# Zotino.net
KiCad netlist of a schematic drawn in Altium Designer
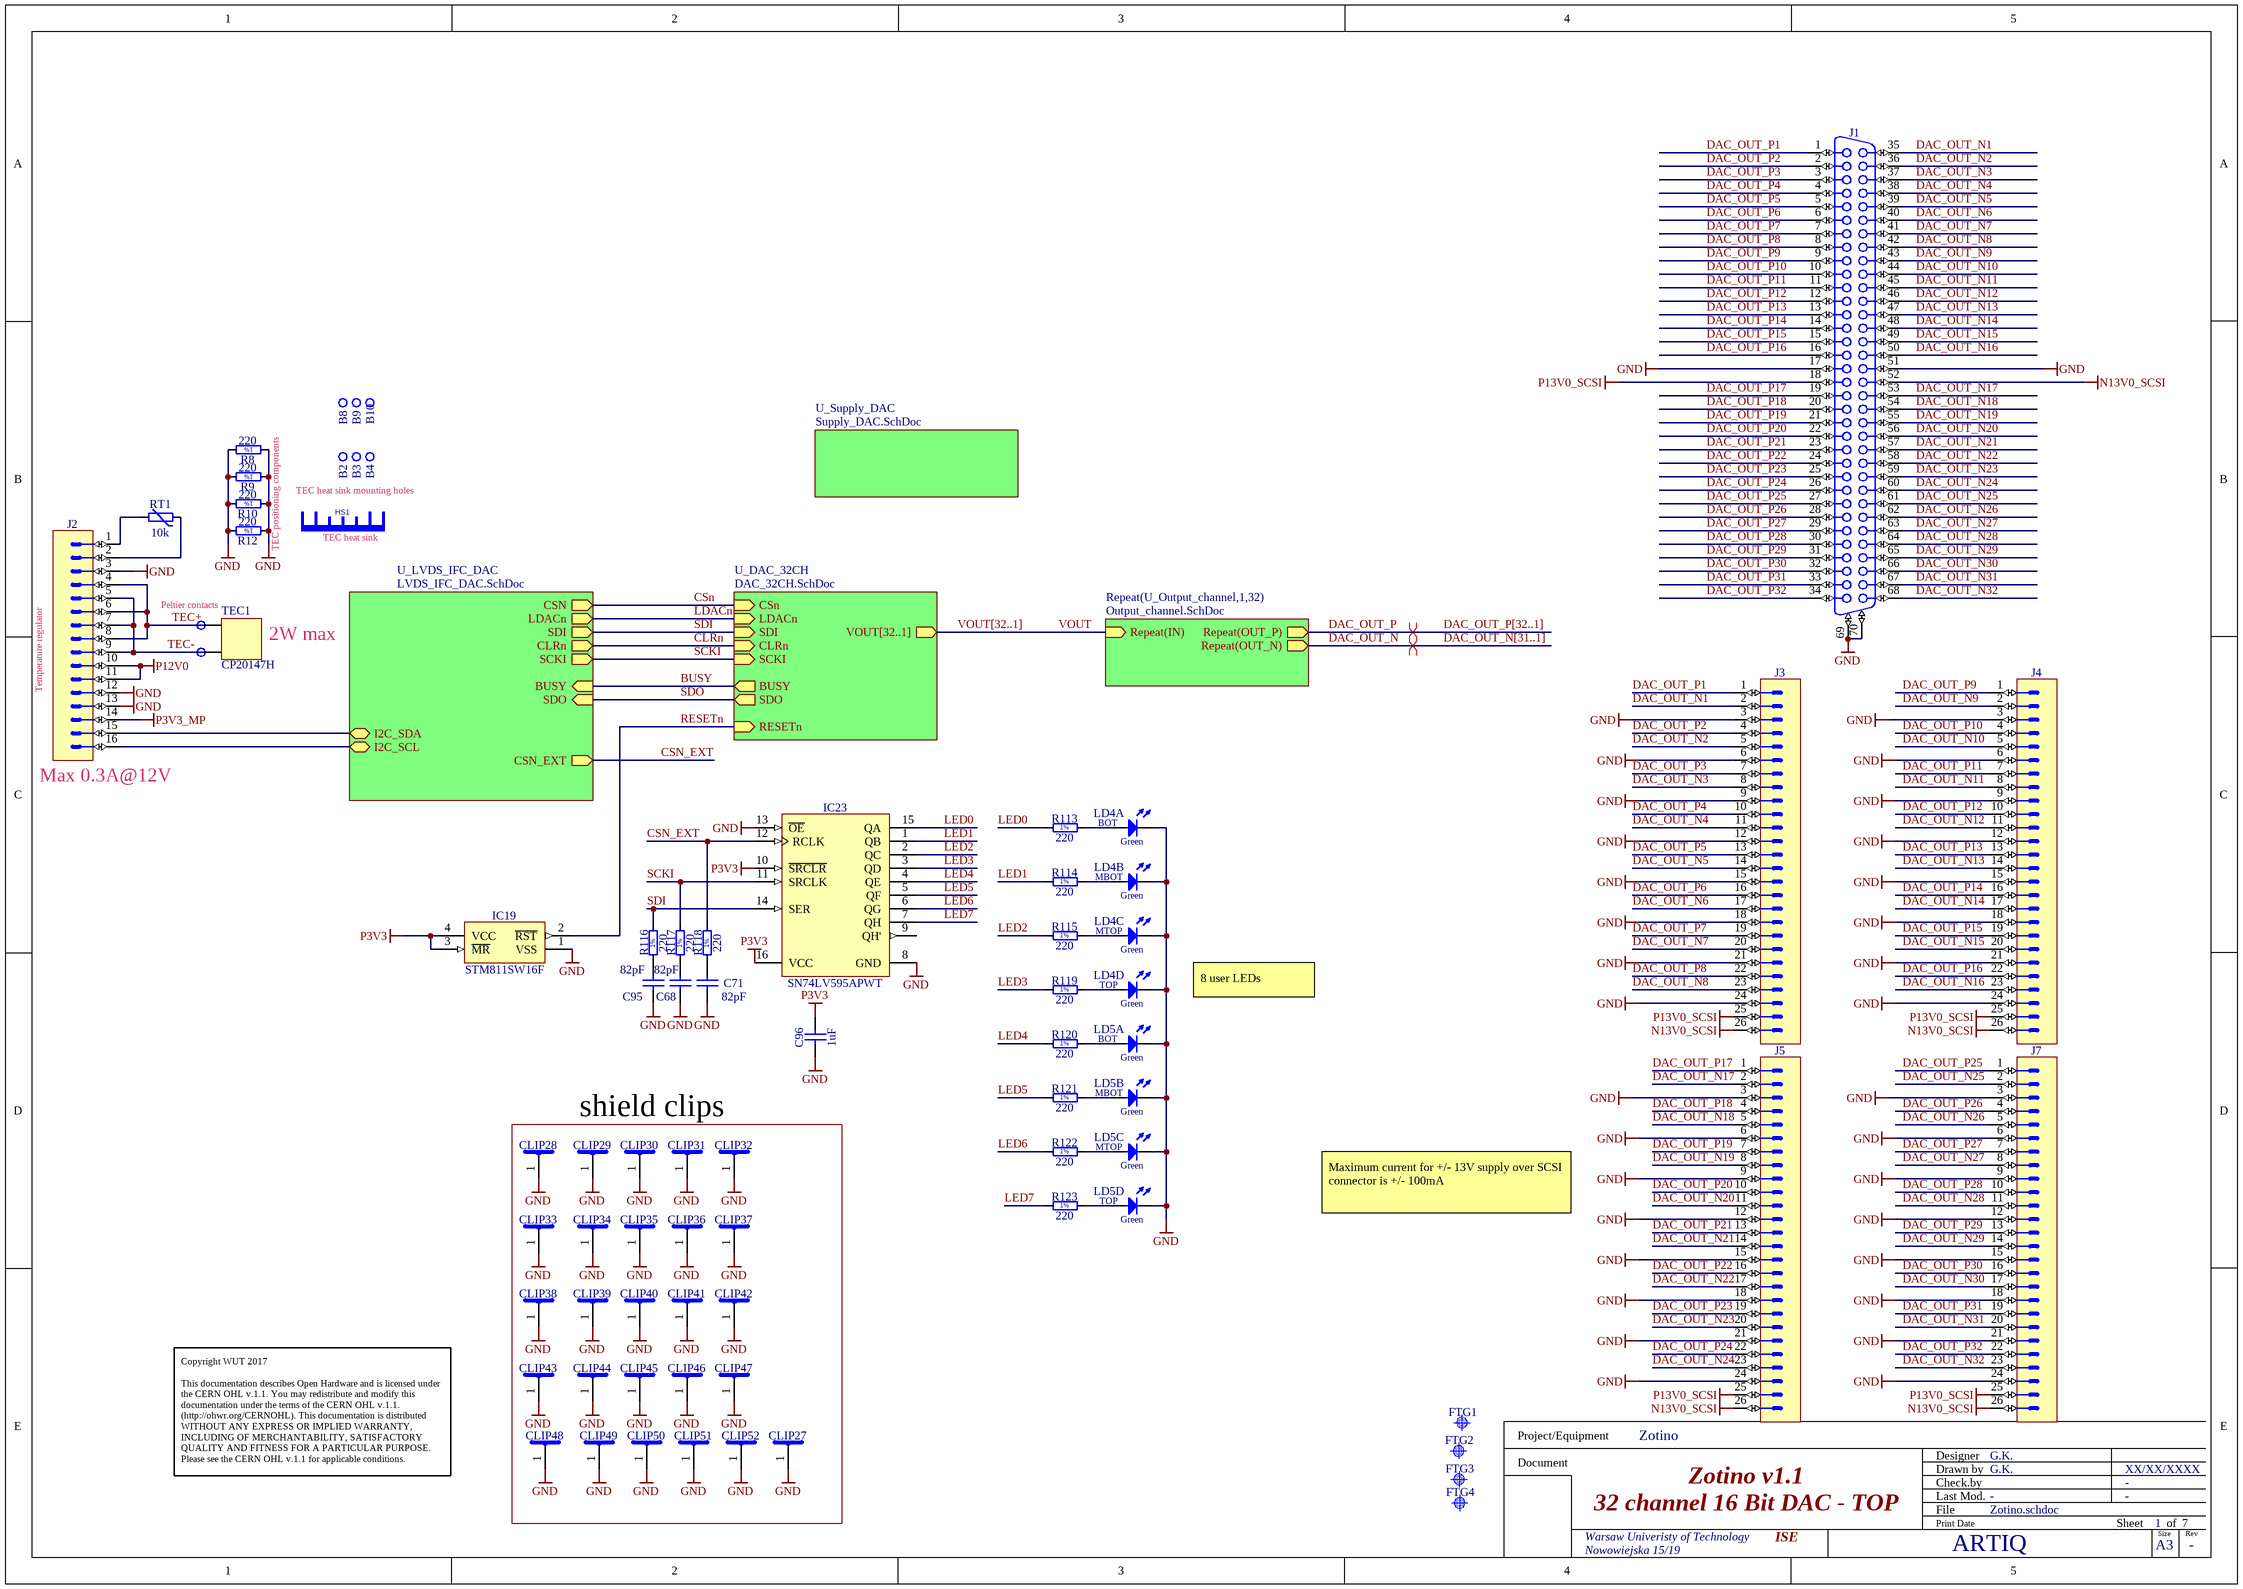
[diagram p0: Zotino.schdoc]

(export (version "E")
  (design (tool "Eeschema 10.0.6"))
  (components
    (comp (ref "B2")
      (value "Plated Hole")
      (footprint "c130h80")
      (description "Single Terminal Socket")
      (fields (field (name "PART NUMBER") "PLATED_HOLE0.8_PAD1.3") (field (name "AUTHOR") "CERN DEM JLC"))
      (libsource (lib "Eletro-mechanical") (part "Single Terminal Socket"))
    )
    (comp (ref "B3")
      (value "Plated Hole")
      (footprint "c130h80")
      (description "Single Terminal Socket")
      (fields (field (name "PART NUMBER") "PLATED_HOLE0.8_PAD1.3") (field (name "AUTHOR") "CERN DEM JLC"))
      (libsource (lib "Eletro-mechanical") (part "Single Terminal Socket"))
    )
    (comp (ref "B4")
      (value "Plated Hole")
      (footprint "c130h80")
      (description "Single Terminal Socket")
      (fields (field (name "PART NUMBER") "PLATED_HOLE0.8_PAD1.3") (field (name "AUTHOR") "CERN DEM JLC"))
      (libsource (lib "Eletro-mechanical") (part "Single Terminal Socket"))
    )
    (comp (ref "B5")
      (value "Plated Hole")
      (footprint "c160h110")
      (description "Single Terminal Socket")
      (fields (field (name "PART NUMBER") "PLATED_HOLE1.1_PAD1.6") (field (name "AUTHOR") "CERN DEM JLC"))
      (libsource (lib "Eletro-mechanical") (part "Single Terminal Socket"))
    )
    (comp (ref "B6")
      (value "Plated Hole")
      (footprint "c160h110")
      (description "Single Terminal Socket")
      (fields (field (name "PART NUMBER") "PLATED_HOLE1.1_PAD1.6") (field (name "AUTHOR") "CERN DEM JLC"))
      (libsource (lib "Eletro-mechanical") (part "Single Terminal Socket"))
    )
    (comp (ref "B8")
      (value "Plated Hole")
      (footprint "c130h80")
      (description "Single Terminal Socket")
      (fields (field (name "PART NUMBER") "PLATED_HOLE0.8_PAD1.3") (field (name "AUTHOR") "CERN DEM JLC"))
      (libsource (lib "Eletro-mechanical") (part "Single Terminal Socket"))
    )
    (comp (ref "B9")
      (value "Plated Hole")
      (footprint "c130h80")
      (description "Single Terminal Socket")
      (fields (field (name "PART NUMBER") "PLATED_HOLE0.8_PAD1.3") (field (name "AUTHOR") "CERN DEM JLC"))
      (libsource (lib "Eletro-mechanical") (part "Single Terminal Socket"))
    )
    (comp (ref "B10")
      (value "Plated Hole")
      (footprint "c130h80")
      (description "Single Terminal Socket")
      (fields (field (name "PART NUMBER") "PLATED_HOLE0.8_PAD1.3") (field (name "AUTHOR") "CERN DEM JLC"))
      (libsource (lib "Eletro-mechanical") (part "Single Terminal Socket"))
    )
    (comp (ref "C68")
      (value "82pF")
      (footprint "CAPC1608X87N")
      (description "Non-polarised capacitor")
      (fields
        (field (name "PART NUMBER") "CC0603_82PF_50V_5%_NP0")
        (field (name "VOLTAGE") "50V")
        (field (name "AUTHOR") "CERN DEM JLC")
      )
      (libsource (lib "Capacitors") (part "Capacitor - non polarized"))
    )
    (comp (ref "C71")
      (value "82pF")
      (footprint "CAPC1608X87N")
      (description "Non-polarised capacitor")
      (fields
        (field (name "PART NUMBER") "CC0603_82PF_50V_5%_NP0")
        (field (name "VOLTAGE") "50V")
        (field (name "AUTHOR") "CERN DEM JLC")
      )
      (libsource (lib "Capacitors") (part "Capacitor - non polarized"))
    )
    (comp (ref "C95")
      (value "82pF")
      (footprint "CAPC1608X87N")
      (description "Non-polarised capacitor")
      (fields
        (field (name "PART NUMBER") "CC0603_82PF_50V_5%_NP0")
        (field (name "VOLTAGE") "50V")
        (field (name "AUTHOR") "CERN DEM JLC")
      )
      (libsource (lib "Capacitors") (part "Capacitor - non polarized"))
    )
    (comp (ref "C96")
      (value "1uF")
      (footprint "CAPC1608X87N")
      (description "Non-polarised capacitor")
      (fields
        (field (name "PART NUMBER") "CC0603_1UF_25V_10%_X7R")
        (field (name "VOLTAGE") "25V")
        (field (name "AUTHOR") "CERN DEM JLC")
      )
      (libsource (lib "Capacitors") (part "Capacitor - non polarized"))
    )
    (comp (ref "CLIP27")
      (value "S1411-46R")
      (footprint "CLIP_HOLLAND-SHIELDING_LC")
      (description "Surface Mount Clip for PCB Screening Covers")
      (fields (field (name "MANUFACTURER") "HARWIN") (field (name "AUTHOR") "CERN DEM JLC"))
      (libsource (lib "LIBRARY_SCH") (part "SHIELD_CLIP"))
    )
    (comp (ref "CLIP28")
      (value "S1411-46R")
      (footprint "CLIP_HOLLAND-SHIELDING_LC")
      (description "Surface Mount Clip for PCB Screening Covers")
      (fields (field (name "MANUFACTURER") "HARWIN") (field (name "AUTHOR") "CERN DEM JLC"))
      (libsource (lib "LIBRARY_SCH") (part "SHIELD_CLIP"))
    )
    (comp (ref "CLIP29")
      (value "S1411-46R")
      (footprint "CLIP_HOLLAND-SHIELDING_LC")
      (description "Surface Mount Clip for PCB Screening Covers")
      (fields (field (name "MANUFACTURER") "HARWIN") (field (name "AUTHOR") "CERN DEM JLC"))
      (libsource (lib "LIBRARY_SCH") (part "SHIELD_CLIP"))
    )
    (comp (ref "CLIP30")
      (value "S1411-46R")
      (footprint "CLIP_HOLLAND-SHIELDING_LC")
      (description "Surface Mount Clip for PCB Screening Covers")
      (fields (field (name "MANUFACTURER") "HARWIN") (field (name "AUTHOR") "CERN DEM JLC"))
      (libsource (lib "LIBRARY_SCH") (part "SHIELD_CLIP"))
    )
    (comp (ref "CLIP31")
      (value "S1411-46R")
      (footprint "CLIP_HOLLAND-SHIELDING_LC")
      (description "Surface Mount Clip for PCB Screening Covers")
      (fields (field (name "MANUFACTURER") "HARWIN") (field (name "AUTHOR") "CERN DEM JLC"))
      (libsource (lib "LIBRARY_SCH") (part "SHIELD_CLIP"))
    )
    (comp (ref "CLIP32")
      (value "S1411-46R")
      (footprint "CLIP_HOLLAND-SHIELDING_LC")
      (description "Surface Mount Clip for PCB Screening Covers")
      (fields (field (name "MANUFACTURER") "HARWIN") (field (name "AUTHOR") "CERN DEM JLC"))
      (libsource (lib "LIBRARY_SCH") (part "SHIELD_CLIP"))
    )
    (comp (ref "CLIP33")
      (value "S1411-46R")
      (footprint "CLIP_HOLLAND-SHIELDING_LC")
      (description "Surface Mount Clip for PCB Screening Covers")
      (fields (field (name "MANUFACTURER") "HARWIN") (field (name "AUTHOR") "CERN DEM JLC"))
      (libsource (lib "LIBRARY_SCH") (part "SHIELD_CLIP"))
    )
    (comp (ref "CLIP34")
      (value "S1411-46R")
      (footprint "CLIP_HOLLAND-SHIELDING_LC")
      (description "Surface Mount Clip for PCB Screening Covers")
      (fields (field (name "MANUFACTURER") "HARWIN") (field (name "AUTHOR") "CERN DEM JLC"))
      (libsource (lib "LIBRARY_SCH") (part "SHIELD_CLIP"))
    )
    (comp (ref "CLIP35")
      (value "S1411-46R")
      (footprint "CLIP_HOLLAND-SHIELDING_LC")
      (description "Surface Mount Clip for PCB Screening Covers")
      (fields (field (name "MANUFACTURER") "HARWIN") (field (name "AUTHOR") "CERN DEM JLC"))
      (libsource (lib "LIBRARY_SCH") (part "SHIELD_CLIP"))
    )
    (comp (ref "CLIP36")
      (value "S1411-46R")
      (footprint "CLIP_HOLLAND-SHIELDING_LC")
      (description "Surface Mount Clip for PCB Screening Covers")
      (fields (field (name "MANUFACTURER") "HARWIN") (field (name "AUTHOR") "CERN DEM JLC"))
      (libsource (lib "LIBRARY_SCH") (part "SHIELD_CLIP"))
    )
    (comp (ref "CLIP37")
      (value "S1411-46R")
      (footprint "CLIP_HOLLAND-SHIELDING_LC")
      (description "Surface Mount Clip for PCB Screening Covers")
      (fields (field (name "MANUFACTURER") "HARWIN") (field (name "AUTHOR") "CERN DEM JLC"))
      (libsource (lib "LIBRARY_SCH") (part "SHIELD_CLIP"))
    )
    (comp (ref "CLIP38")
      (value "S1411-46R")
      (footprint "CLIP_HOLLAND-SHIELDING_LC")
      (description "Surface Mount Clip for PCB Screening Covers")
      (fields (field (name "MANUFACTURER") "HARWIN") (field (name "AUTHOR") "CERN DEM JLC"))
      (libsource (lib "LIBRARY_SCH") (part "SHIELD_CLIP"))
    )
    (comp (ref "CLIP39")
      (value "S1411-46R")
      (footprint "CLIP_HOLLAND-SHIELDING_LC")
      (description "Surface Mount Clip for PCB Screening Covers")
      (fields (field (name "MANUFACTURER") "HARWIN") (field (name "AUTHOR") "CERN DEM JLC"))
      (libsource (lib "LIBRARY_SCH") (part "SHIELD_CLIP"))
    )
    (comp (ref "CLIP40")
      (value "S1411-46R")
      (footprint "CLIP_HOLLAND-SHIELDING_LC")
      (description "Surface Mount Clip for PCB Screening Covers")
      (fields (field (name "MANUFACTURER") "HARWIN") (field (name "AUTHOR") "CERN DEM JLC"))
      (libsource (lib "LIBRARY_SCH") (part "SHIELD_CLIP"))
    )
    (comp (ref "CLIP41")
      (value "S1411-46R")
      (footprint "CLIP_HOLLAND-SHIELDING_LC")
      (description "Surface Mount Clip for PCB Screening Covers")
      (fields (field (name "MANUFACTURER") "HARWIN") (field (name "AUTHOR") "CERN DEM JLC"))
      (libsource (lib "LIBRARY_SCH") (part "SHIELD_CLIP"))
    )
    (comp (ref "CLIP42")
      (value "S1411-46R")
      (footprint "CLIP_HOLLAND-SHIELDING_LC")
      (description "Surface Mount Clip for PCB Screening Covers")
      (fields (field (name "MANUFACTURER") "HARWIN") (field (name "AUTHOR") "CERN DEM JLC"))
      (libsource (lib "LIBRARY_SCH") (part "SHIELD_CLIP"))
    )
    (comp (ref "CLIP43")
      (value "S1411-46R")
      (footprint "CLIP_HOLLAND-SHIELDING_LC")
      (description "Surface Mount Clip for PCB Screening Covers")
      (fields (field (name "MANUFACTURER") "HARWIN") (field (name "AUTHOR") "CERN DEM JLC"))
      (libsource (lib "LIBRARY_SCH") (part "SHIELD_CLIP"))
    )
    (comp (ref "CLIP44")
      (value "S1411-46R")
      (footprint "CLIP_HOLLAND-SHIELDING_LC")
      (description "Surface Mount Clip for PCB Screening Covers")
      (fields (field (name "MANUFACTURER") "HARWIN") (field (name "AUTHOR") "CERN DEM JLC"))
      (libsource (lib "LIBRARY_SCH") (part "SHIELD_CLIP"))
    )
    (comp (ref "CLIP45")
      (value "S1411-46R")
      (footprint "CLIP_HOLLAND-SHIELDING_LC")
      (description "Surface Mount Clip for PCB Screening Covers")
      (fields (field (name "MANUFACTURER") "HARWIN") (field (name "AUTHOR") "CERN DEM JLC"))
      (libsource (lib "LIBRARY_SCH") (part "SHIELD_CLIP"))
    )
    (comp (ref "CLIP46")
      (value "S1411-46R")
      (footprint "CLIP_HOLLAND-SHIELDING_LC")
      (description "Surface Mount Clip for PCB Screening Covers")
      (fields (field (name "MANUFACTURER") "HARWIN") (field (name "AUTHOR") "CERN DEM JLC"))
      (libsource (lib "LIBRARY_SCH") (part "SHIELD_CLIP"))
    )
    (comp (ref "CLIP47")
      (value "S1411-46R")
      (footprint "CLIP_HOLLAND-SHIELDING_LC")
      (description "Surface Mount Clip for PCB Screening Covers")
      (fields (field (name "MANUFACTURER") "HARWIN") (field (name "AUTHOR") "CERN DEM JLC"))
      (libsource (lib "LIBRARY_SCH") (part "SHIELD_CLIP"))
    )
    (comp (ref "CLIP48")
      (value "S1411-46R")
      (footprint "CLIP_HOLLAND-SHIELDING_LC")
      (description "Surface Mount Clip for PCB Screening Covers")
      (fields (field (name "MANUFACTURER") "HARWIN") (field (name "AUTHOR") "CERN DEM JLC"))
      (libsource (lib "LIBRARY_SCH") (part "SHIELD_CLIP"))
    )
    (comp (ref "CLIP49")
      (value "S1411-46R")
      (footprint "CLIP_HOLLAND-SHIELDING_LC")
      (description "Surface Mount Clip for PCB Screening Covers")
      (fields (field (name "MANUFACTURER") "HARWIN") (field (name "AUTHOR") "CERN DEM JLC"))
      (libsource (lib "LIBRARY_SCH") (part "SHIELD_CLIP"))
    )
    (comp (ref "CLIP50")
      (value "S1411-46R")
      (footprint "CLIP_HOLLAND-SHIELDING_LC")
      (description "Surface Mount Clip for PCB Screening Covers")
      (fields (field (name "MANUFACTURER") "HARWIN") (field (name "AUTHOR") "CERN DEM JLC"))
      (libsource (lib "LIBRARY_SCH") (part "SHIELD_CLIP"))
    )
    (comp (ref "CLIP51")
      (value "S1411-46R")
      (footprint "CLIP_HOLLAND-SHIELDING_LC")
      (description "Surface Mount Clip for PCB Screening Covers")
      (fields (field (name "MANUFACTURER") "HARWIN") (field (name "AUTHOR") "CERN DEM JLC"))
      (libsource (lib "LIBRARY_SCH") (part "SHIELD_CLIP"))
    )
    (comp (ref "CLIP52")
      (value "S1411-46R")
      (footprint "CLIP_HOLLAND-SHIELDING_LC")
      (description "Surface Mount Clip for PCB Screening Covers")
      (fields (field (name "MANUFACTURER") "HARWIN") (field (name "AUTHOR") "CERN DEM JLC"))
      (libsource (lib "LIBRARY_SCH") (part "SHIELD_CLIP"))
    )
    (comp (ref "FTG1")
      (value "Use only in PCB")
      (footprint "FIDUCIAL_TOP_C100-200")
      (description "Fiducial Target")
      (fields (field (name "PART NUMBER") "FIDUCIAL_TARGET_C100-200") (field (name "AUTHOR") "CERN DEM JLC"))
      (libsource (lib "Eletro-mechanical") (part "Fiducial Target"))
    )
    (comp (ref "FTG2")
      (value "Use only in PCB")
      (footprint "FIDUCIAL_TOP_S100-200")
      (description "Fiducial Target")
      (fields (field (name "PART NUMBER") "FIDUCIAL_TARGET_S100-200") (field (name "AUTHOR") "CERN DEM JLC"))
      (libsource (lib "Eletro-mechanical") (part "Fiducial Target"))
    )
    (comp (ref "FTG3")
      (value "Use only in PCB")
      (footprint "FIDUCIAL_TOP_S200-400")
      (description "Fiducial Target")
      (fields (field (name "PART NUMBER") "FIDUCIAL_TARGET_S200-400") (field (name "AUTHOR") "CERN DEM JLC"))
      (libsource (lib "Eletro-mechanical") (part "Fiducial Target"))
    )
    (comp (ref "FTG4")
      (value "Use only in PCB")
      (footprint "FIDUCIAL_TOP_S100-200")
      (description "Fiducial Target")
      (fields (field (name "PART NUMBER") "FIDUCIAL_TARGET_S100-200") (field (name "AUTHOR") "CERN DEM JLC"))
      (libsource (lib "Eletro-mechanical") (part "Fiducial Target"))
    )
    (comp (ref "HS1")
      (value "Heat Sink No Pad")
      (footprint "HSINK_ATS_ATS-X50190G-C1-R0")
      (description "Heat Sink Without Pad")
      (fields
        (field (name "PART NUMBER") "HSINK_ATS_ATS-X50190G-C1-R0")
        (field (name "MANUFACTURER") "ADVENCED THERMAL SOLUTION (ATS)")
        (field (name "AUTHOR") "GK")
      )
      (libsource (lib "LIBRARY_SCH") (part "HEAT_SINK_19x19"))
    )
    (comp (ref "IC19")
      (value "STM811SW16F")
      (footprint "SOT143N")
      (description "Microprocessor Reset Circuit")
      (fields (field (name "MANUFACTURER") "ST MICROELECTRONICS") (field (name "AUTHOR") "CERN DEM JLC"))
      (libsource (lib "ICs And Semiconductors") (part "STM811"))
    )
    (comp (ref "IC23")
      (value "SN74LV595APWT")
      (footprint "SOP65P640X120-16N")
      (description "8-Bit Shift Register With 3-State Output Register")
      (fields (field (name "MANUFACTURER") "TEXAS INSTRUMENTS") (field (name "AUTHOR") "CERN DEM JLC"))
      (libsource (lib "ICs And Semiconductors") (part "74595"))
    )
    (comp (ref "J1")
      (value "D-SUB")
      (footprint "TYCO_5787082-7")
      (description "68 contacts, AMPLIMITE .050\", Right Angled Receptacle Series III")
      (fields
        (field (name "PART NUMBER") "TYCO_5787082-7")
        (field (name "MANUFACTURER") "TYCO ELECTRONICS")
        (field (name "AUTHOR") "CERN DEM JLC")
      )
      (libsource (lib "Connectors") (part "TYCO_5787082-7"))
    )
    (comp (ref "J2")
      (value "Header 16")
      (footprint "3M_N2516-6002RB")
      (description "Connector 16 Male")
      (fields
        (field (name "PART NUMBER") "3M_N2516-6002RB")
        (field (name "MANUFACTURER") "3M")
        (field (name "AUTHOR") "CERN DEM JLC")
      )
      (libsource (lib "Connectors") (part "Connector 16 Male"))
    )
    (comp (ref "J3")
      (value "Header 26")
      (footprint "3M_N2526-6002RB")
      (description "Connector 26 Male")
      (fields
        (field (name "PART NUMBER") "3M_N2526-6002RB")
        (field (name "MANUFACTURER") "3M")
        (field (name "AUTHOR") "CERN DEM JLC")
      )
      (libsource (lib "Connectors") (part "Connector 26 Male"))
    )
    (comp (ref "J4")
      (value "Header 26")
      (footprint "3M_N2526-6002RB")
      (description "Connector 26 Male")
      (fields
        (field (name "PART NUMBER") "3M_N2526-6002RB")
        (field (name "MANUFACTURER") "3M")
        (field (name "AUTHOR") "CERN DEM JLC")
      )
      (libsource (lib "Connectors") (part "Connector 26 Male"))
    )
    (comp (ref "J5")
      (value "Header 26")
      (footprint "3M_N2526-6002RB")
      (description "Connector 26 Male")
      (fields
        (field (name "PART NUMBER") "3M_N2526-6002RB")
        (field (name "MANUFACTURER") "3M")
        (field (name "AUTHOR") "CERN DEM JLC")
      )
      (libsource (lib "Connectors") (part "Connector 26 Male"))
    )
    (comp (ref "J7")
      (value "Header 26")
      (footprint "3M_N2526-6002RB")
      (description "Connector 26 Male")
      (fields
        (field (name "PART NUMBER") "3M_N2526-6002RB")
        (field (name "MANUFACTURER") "3M")
        (field (name "AUTHOR") "CERN DEM JLC")
      )
      (libsource (lib "Connectors") (part "Connector 26 Male"))
    )
    (comp (ref "LD4")
      (value "Green")
      (footprint "LED_BIVAR_H485CGDL")
      (description "LED x4 Green 1C2A-BOT_3C4A_5C6A_7C8A-TOP")
      (fields
        (field (name "PART NUMBER") "LED_BIVAR_H485CGDL")
        (field (name "MANUFACTURER") "BIVAR")
        (field (name "AUTHOR") "CERN DEM JLC")
      )
      (libsource (lib "ICs And Semiconductors") (part "LED x4 Green 1C2A-BOT_3C4A_5C6A_7C8A-TOP"))
    )
    (comp (ref "LD5")
      (value "Green")
      (footprint "LED_BIVAR_H485CGDL")
      (description "LED x4 Green 1C2A-BOT_3C4A_5C6A_7C8A-TOP")
      (fields
        (field (name "PART NUMBER") "LED_BIVAR_H485CGDL")
        (field (name "MANUFACTURER") "BIVAR")
        (field (name "AUTHOR") "CERN DEM JLC")
      )
      (libsource (lib "ICs And Semiconductors") (part "LED x4 Green 1C2A-BOT_3C4A_5C6A_7C8A-TOP"))
    )
    (comp (ref "R8")
      (value "220")
      (footprint "RESC1608X55N")
      (description "Resistor - 1%")
      (fields
        (field (name "PART NUMBER") "R0603_220R_1%_0.1W_100PPM")
        (field (name "POWER") "0.1W")
        (field (name "AUTHOR") "CERN DEM JLC")
      )
      (libsource (lib "Resistors") (part "Resistor - 1%"))
    )
    (comp (ref "R9")
      (value "220")
      (footprint "RESC1608X55N")
      (description "Resistor - 1%")
      (fields
        (field (name "PART NUMBER") "R0603_220R_1%_0.1W_100PPM")
        (field (name "POWER") "0.1W")
        (field (name "AUTHOR") "CERN DEM JLC")
      )
      (libsource (lib "Resistors") (part "Resistor - 1%"))
    )
    (comp (ref "R10")
      (value "220")
      (footprint "RESC1608X55N")
      (description "Resistor - 1%")
      (fields
        (field (name "PART NUMBER") "R0603_220R_1%_0.1W_100PPM")
        (field (name "POWER") "0.1W")
        (field (name "AUTHOR") "CERN DEM JLC")
      )
      (libsource (lib "Resistors") (part "Resistor - 1%"))
    )
    (comp (ref "R12")
      (value "220")
      (footprint "RESC1608X55N")
      (description "Resistor - 1%")
      (fields
        (field (name "PART NUMBER") "R0603_220R_1%_0.1W_100PPM")
        (field (name "POWER") "0.1W")
        (field (name "AUTHOR") "CERN DEM JLC")
      )
      (libsource (lib "Resistors") (part "Resistor - 1%"))
    )
    (comp (ref "R113")
      (value "220")
      (footprint "RESC1608X55N")
      (description "Resistor - 1%")
      (fields
        (field (name "PART NUMBER") "R0603_220R_1%_0.1W_100PPM")
        (field (name "POWER") "0.1W")
        (field (name "AUTHOR") "CERN DEM JLC")
      )
      (libsource (lib "Resistors") (part "Resistor - 1%"))
    )
    (comp (ref "R114")
      (value "220")
      (footprint "RESC1608X55N")
      (description "Resistor - 1%")
      (fields
        (field (name "PART NUMBER") "R0603_220R_1%_0.1W_100PPM")
        (field (name "POWER") "0.1W")
        (field (name "AUTHOR") "CERN DEM JLC")
      )
      (libsource (lib "Resistors") (part "Resistor - 1%"))
    )
    (comp (ref "R115")
      (value "220")
      (footprint "RESC1608X55N")
      (description "Resistor - 1%")
      (fields
        (field (name "PART NUMBER") "R0603_220R_1%_0.1W_100PPM")
        (field (name "POWER") "0.1W")
        (field (name "AUTHOR") "CERN DEM JLC")
      )
      (libsource (lib "Resistors") (part "Resistor - 1%"))
    )
    (comp (ref "R116")
      (value "220")
      (footprint "RESC1608X55N")
      (description "Resistor - 1%")
      (fields
        (field (name "PART NUMBER") "R0603_220R_1%_0.1W_100PPM")
        (field (name "POWER") "0.1W")
        (field (name "AUTHOR") "CERN DEM JLC")
      )
      (libsource (lib "Resistors") (part "Resistor - 1%"))
    )
    (comp (ref "R117")
      (value "220")
      (footprint "RESC1608X55N")
      (description "Resistor - 1%")
      (fields
        (field (name "PART NUMBER") "R0603_220R_1%_0.1W_100PPM")
        (field (name "POWER") "0.1W")
        (field (name "AUTHOR") "CERN DEM JLC")
      )
      (libsource (lib "Resistors") (part "Resistor - 1%"))
    )
    (comp (ref "R118")
      (value "220")
      (footprint "RESC1608X55N")
      (description "Resistor - 1%")
      (fields
        (field (name "PART NUMBER") "R0603_220R_1%_0.1W_100PPM")
        (field (name "POWER") "0.1W")
        (field (name "AUTHOR") "CERN DEM JLC")
      )
      (libsource (lib "Resistors") (part "Resistor - 1%"))
    )
    (comp (ref "R119")
      (value "220")
      (footprint "RESC1608X55N")
      (description "Resistor - 1%")
      (fields
        (field (name "PART NUMBER") "R0603_220R_1%_0.1W_100PPM")
        (field (name "POWER") "0.1W")
        (field (name "AUTHOR") "CERN DEM JLC")
      )
      (libsource (lib "Resistors") (part "Resistor - 1%"))
    )
    (comp (ref "R120")
      (value "220")
      (footprint "RESC1608X55N")
      (description "Resistor - 1%")
      (fields
        (field (name "PART NUMBER") "R0603_220R_1%_0.1W_100PPM")
        (field (name "POWER") "0.1W")
        (field (name "AUTHOR") "CERN DEM JLC")
      )
      (libsource (lib "Resistors") (part "Resistor - 1%"))
    )
    (comp (ref "R121")
      (value "220")
      (footprint "RESC1608X55N")
      (description "Resistor - 1%")
      (fields
        (field (name "PART NUMBER") "R0603_220R_1%_0.1W_100PPM")
        (field (name "POWER") "0.1W")
        (field (name "AUTHOR") "CERN DEM JLC")
      )
      (libsource (lib "Resistors") (part "Resistor - 1%"))
    )
    (comp (ref "R122")
      (value "220")
      (footprint "RESC1608X55N")
      (description "Resistor - 1%")
      (fields
        (field (name "PART NUMBER") "R0603_220R_1%_0.1W_100PPM")
        (field (name "POWER") "0.1W")
        (field (name "AUTHOR") "CERN DEM JLC")
      )
      (libsource (lib "Resistors") (part "Resistor - 1%"))
    )
    (comp (ref "R123")
      (value "220")
      (footprint "RESC1608X55N")
      (description "Resistor - 1%")
      (fields
        (field (name "PART NUMBER") "R0603_220R_1%_0.1W_100PPM")
        (field (name "POWER") "0.1W")
        (field (name "AUTHOR") "CERN DEM JLC")
      )
      (libsource (lib "Resistors") (part "Resistor - 1%"))
    )
    (comp (ref "RT1")
      (value "10k")
      (footprint "THERMC1608X90N")
      (description "Thermistor NTC (Negative Temperature Coefficient)")
      (fields
        (field (name "PART NUMBER") "THERM_NTC_10K_EPCOS_B57330V2103J260")
        (field (name "POWER") "180mW")
        (field (name "AUTHOR") "CERN DEM BC")
      )
      (libsource (lib "Resistors") (part "Thermistor NTC"))
    )
    (comp (ref "TEC1")
      (value "CP20147H")
      (footprint "TEC_CP20147H")
      (description "Peltier Module 15x15 mm")
      (libsource (lib "LIBRARY_SCH") (part "TEC_CP20147H"))
    )
  )
  (nets
    (net (code "35") (name "/CSN_EXT") (class "Default")
      (node (ref "IC23") (pin "12") (pinfunction "RCLK_12") (pintype "input"))
      (node (ref "R118") (pin "2") (pinfunction "2_2") (pintype "passive"))
    )
    (net (code "38") (name "/DAC_OUT_N1") (class "Default")
      (node (ref "J1") (pin "35") (pinfunction "35_35") (pintype "bidirectional"))
      (node (ref "J3") (pin "2") (pinfunction "2_2") (pintype "bidirectional"))
    )
    (net (code "39") (name "/DAC_OUT_N2") (class "Default")
      (node (ref "J1") (pin "36") (pinfunction "36_36") (pintype "bidirectional"))
      (node (ref "J3") (pin "5") (pinfunction "5_5") (pintype "bidirectional"))
    )
    (net (code "40") (name "/DAC_OUT_N3") (class "Default")
      (node (ref "J1") (pin "37") (pinfunction "37_37") (pintype "bidirectional"))
      (node (ref "J3") (pin "8") (pinfunction "8_8") (pintype "bidirectional"))
    )
    (net (code "41") (name "/DAC_OUT_N4") (class "Default")
      (node (ref "J1") (pin "38") (pinfunction "38_38") (pintype "bidirectional"))
      (node (ref "J3") (pin "11") (pinfunction "11_11") (pintype "bidirectional"))
    )
    (net (code "42") (name "/DAC_OUT_N5") (class "Default")
      (node (ref "J1") (pin "39") (pinfunction "39_39") (pintype "bidirectional"))
      (node (ref "J3") (pin "14") (pinfunction "14_14") (pintype "bidirectional"))
    )
    (net (code "43") (name "/DAC_OUT_N6") (class "Default")
      (node (ref "J1") (pin "40") (pinfunction "40_40") (pintype "bidirectional"))
      (node (ref "J3") (pin "17") (pinfunction "17_17") (pintype "bidirectional"))
    )
    (net (code "44") (name "/DAC_OUT_N7") (class "Default")
      (node (ref "J1") (pin "41") (pinfunction "41_41") (pintype "bidirectional"))
      (node (ref "J3") (pin "20") (pinfunction "20_20") (pintype "bidirectional"))
    )
    (net (code "45") (name "/DAC_OUT_N8") (class "Default")
      (node (ref "J1") (pin "42") (pinfunction "42_42") (pintype "bidirectional"))
      (node (ref "J3") (pin "23") (pinfunction "23_23") (pintype "bidirectional"))
    )
    (net (code "46") (name "/DAC_OUT_N9") (class "Default")
      (node (ref "J1") (pin "43") (pinfunction "43_43") (pintype "bidirectional"))
      (node (ref "J4") (pin "2") (pinfunction "2_2") (pintype "bidirectional"))
    )
    (net (code "47") (name "/DAC_OUT_N10") (class "Default")
      (node (ref "J1") (pin "44") (pinfunction "44_44") (pintype "bidirectional"))
      (node (ref "J4") (pin "5") (pinfunction "5_5") (pintype "bidirectional"))
    )
    (net (code "48") (name "/DAC_OUT_N11") (class "Default")
      (node (ref "J1") (pin "45") (pinfunction "45_45") (pintype "bidirectional"))
      (node (ref "J4") (pin "8") (pinfunction "8_8") (pintype "bidirectional"))
    )
    (net (code "49") (name "/DAC_OUT_N12") (class "Default")
      (node (ref "J1") (pin "46") (pinfunction "46_46") (pintype "bidirectional"))
      (node (ref "J4") (pin "11") (pinfunction "11_11") (pintype "bidirectional"))
    )
    (net (code "50") (name "/DAC_OUT_N13") (class "Default")
      (node (ref "J1") (pin "47") (pinfunction "47_47") (pintype "bidirectional"))
      (node (ref "J4") (pin "14") (pinfunction "14_14") (pintype "bidirectional"))
    )
    (net (code "51") (name "/DAC_OUT_N14") (class "Default")
      (node (ref "J1") (pin "48") (pinfunction "48_48") (pintype "bidirectional"))
      (node (ref "J4") (pin "17") (pinfunction "17_17") (pintype "bidirectional"))
    )
    (net (code "52") (name "/DAC_OUT_N15") (class "Default")
      (node (ref "J1") (pin "49") (pinfunction "49_49") (pintype "bidirectional"))
      (node (ref "J4") (pin "20") (pinfunction "20_20") (pintype "bidirectional"))
    )
    (net (code "53") (name "/DAC_OUT_N16") (class "Default")
      (node (ref "J1") (pin "50") (pinfunction "50_50") (pintype "bidirectional"))
      (node (ref "J4") (pin "23") (pinfunction "23_23") (pintype "bidirectional"))
    )
    (net (code "54") (name "/DAC_OUT_N17") (class "Default")
      (node (ref "J1") (pin "53") (pinfunction "53_53") (pintype "bidirectional"))
      (node (ref "J5") (pin "2") (pinfunction "2_2") (pintype "bidirectional"))
    )
    (net (code "55") (name "/DAC_OUT_N18") (class "Default")
      (node (ref "J1") (pin "54") (pinfunction "54_54") (pintype "bidirectional"))
      (node (ref "J5") (pin "5") (pinfunction "5_5") (pintype "bidirectional"))
    )
    (net (code "56") (name "/DAC_OUT_N19") (class "Default")
      (node (ref "J1") (pin "55") (pinfunction "55_55") (pintype "bidirectional"))
      (node (ref "J5") (pin "8") (pinfunction "8_8") (pintype "bidirectional"))
    )
    (net (code "57") (name "/DAC_OUT_N20") (class "Default")
      (node (ref "J1") (pin "56") (pinfunction "56_56") (pintype "bidirectional"))
      (node (ref "J5") (pin "11") (pinfunction "11_11") (pintype "bidirectional"))
    )
    (net (code "58") (name "/DAC_OUT_N21") (class "Default")
      (node (ref "J1") (pin "57") (pinfunction "57_57") (pintype "bidirectional"))
      (node (ref "J5") (pin "14") (pinfunction "14_14") (pintype "bidirectional"))
    )
    (net (code "59") (name "/DAC_OUT_N22") (class "Default")
      (node (ref "J1") (pin "58") (pinfunction "58_58") (pintype "bidirectional"))
      (node (ref "J5") (pin "17") (pinfunction "17_17") (pintype "bidirectional"))
    )
    (net (code "60") (name "/DAC_OUT_N23") (class "Default")
      (node (ref "J1") (pin "59") (pinfunction "59_59") (pintype "bidirectional"))
      (node (ref "J5") (pin "20") (pinfunction "20_20") (pintype "bidirectional"))
    )
    (net (code "61") (name "/DAC_OUT_N24") (class "Default")
      (node (ref "J1") (pin "60") (pinfunction "60_60") (pintype "bidirectional"))
      (node (ref "J5") (pin "23") (pinfunction "23_23") (pintype "bidirectional"))
    )
    (net (code "62") (name "/DAC_OUT_N25") (class "Default")
      (node (ref "J1") (pin "61") (pinfunction "61_61") (pintype "bidirectional"))
      (node (ref "J7") (pin "2") (pinfunction "2_2") (pintype "bidirectional"))
    )
    (net (code "63") (name "/DAC_OUT_N26") (class "Default")
      (node (ref "J1") (pin "62") (pinfunction "62_62") (pintype "bidirectional"))
      (node (ref "J7") (pin "5") (pinfunction "5_5") (pintype "bidirectional"))
    )
    (net (code "64") (name "/DAC_OUT_N27") (class "Default")
      (node (ref "J1") (pin "63") (pinfunction "63_63") (pintype "bidirectional"))
      (node (ref "J7") (pin "8") (pinfunction "8_8") (pintype "bidirectional"))
    )
    (net (code "65") (name "/DAC_OUT_N28") (class "Default")
      (node (ref "J1") (pin "64") (pinfunction "64_64") (pintype "bidirectional"))
      (node (ref "J7") (pin "11") (pinfunction "11_11") (pintype "bidirectional"))
    )
    (net (code "66") (name "/DAC_OUT_N29") (class "Default")
      (node (ref "J1") (pin "65") (pinfunction "65_65") (pintype "bidirectional"))
      (node (ref "J7") (pin "14") (pinfunction "14_14") (pintype "bidirectional"))
    )
    (net (code "67") (name "/DAC_OUT_N30") (class "Default")
      (node (ref "J1") (pin "66") (pinfunction "66_66") (pintype "bidirectional"))
      (node (ref "J7") (pin "17") (pinfunction "17_17") (pintype "bidirectional"))
    )
    (net (code "68") (name "/DAC_OUT_N31") (class "Default")
      (node (ref "J1") (pin "67") (pinfunction "67_67") (pintype "bidirectional"))
      (node (ref "J7") (pin "20") (pinfunction "20_20") (pintype "bidirectional"))
    )
    (net (code "69") (name "/DAC_OUT_N32") (class "Default")
      (node (ref "J1") (pin "68") (pinfunction "68_68") (pintype "bidirectional"))
      (node (ref "J7") (pin "23") (pinfunction "23_23") (pintype "bidirectional"))
    )
    (net (code "72") (name "/DAC_OUT_P1") (class "Default")
      (node (ref "J1") (pin "1") (pinfunction "1_1") (pintype "bidirectional"))
      (node (ref "J3") (pin "1") (pinfunction "1_1") (pintype "bidirectional"))
    )
    (net (code "73") (name "/DAC_OUT_P2") (class "Default")
      (node (ref "J1") (pin "2") (pinfunction "2_2") (pintype "bidirectional"))
      (node (ref "J3") (pin "4") (pinfunction "4_4") (pintype "bidirectional"))
    )
    (net (code "74") (name "/DAC_OUT_P3") (class "Default")
      (node (ref "J1") (pin "3") (pinfunction "3_3") (pintype "bidirectional"))
      (node (ref "J3") (pin "7") (pinfunction "7_7") (pintype "bidirectional"))
    )
    (net (code "75") (name "/DAC_OUT_P4") (class "Default")
      (node (ref "J1") (pin "4") (pinfunction "4_4") (pintype "bidirectional"))
      (node (ref "J3") (pin "10") (pinfunction "10_10") (pintype "bidirectional"))
    )
    (net (code "76") (name "/DAC_OUT_P5") (class "Default")
      (node (ref "J1") (pin "5") (pinfunction "5_5") (pintype "bidirectional"))
      (node (ref "J3") (pin "13") (pinfunction "13_13") (pintype "bidirectional"))
    )
    (net (code "77") (name "/DAC_OUT_P6") (class "Default")
      (node (ref "J1") (pin "6") (pinfunction "6_6") (pintype "bidirectional"))
      (node (ref "J3") (pin "16") (pinfunction "16_16") (pintype "bidirectional"))
    )
    (net (code "78") (name "/DAC_OUT_P7") (class "Default")
      (node (ref "J1") (pin "7") (pinfunction "7_7") (pintype "bidirectional"))
      (node (ref "J3") (pin "19") (pinfunction "19_19") (pintype "bidirectional"))
    )
    (net (code "79") (name "/DAC_OUT_P8") (class "Default")
      (node (ref "J1") (pin "8") (pinfunction "8_8") (pintype "bidirectional"))
      (node (ref "J3") (pin "22") (pinfunction "22_22") (pintype "bidirectional"))
    )
    (net (code "80") (name "/DAC_OUT_P9") (class "Default")
      (node (ref "J1") (pin "9") (pinfunction "9_9") (pintype "bidirectional"))
      (node (ref "J4") (pin "1") (pinfunction "1_1") (pintype "bidirectional"))
    )
    (net (code "81") (name "/DAC_OUT_P10") (class "Default")
      (node (ref "J1") (pin "10") (pinfunction "10_10") (pintype "bidirectional"))
      (node (ref "J4") (pin "4") (pinfunction "4_4") (pintype "bidirectional"))
    )
    (net (code "82") (name "/DAC_OUT_P11") (class "Default")
      (node (ref "J1") (pin "11") (pinfunction "11_11") (pintype "bidirectional"))
      (node (ref "J4") (pin "7") (pinfunction "7_7") (pintype "bidirectional"))
    )
    (net (code "83") (name "/DAC_OUT_P12") (class "Default")
      (node (ref "J1") (pin "12") (pinfunction "12_12") (pintype "bidirectional"))
      (node (ref "J4") (pin "10") (pinfunction "10_10") (pintype "bidirectional"))
    )
    (net (code "84") (name "/DAC_OUT_P13") (class "Default")
      (node (ref "J1") (pin "13") (pinfunction "13_13") (pintype "bidirectional"))
      (node (ref "J4") (pin "13") (pinfunction "13_13") (pintype "bidirectional"))
    )
    (net (code "85") (name "/DAC_OUT_P14") (class "Default")
      (node (ref "J1") (pin "14") (pinfunction "14_14") (pintype "bidirectional"))
      (node (ref "J4") (pin "16") (pinfunction "16_16") (pintype "bidirectional"))
    )
    (net (code "86") (name "/DAC_OUT_P15") (class "Default")
      (node (ref "J1") (pin "15") (pinfunction "15_15") (pintype "bidirectional"))
      (node (ref "J4") (pin "19") (pinfunction "19_19") (pintype "bidirectional"))
    )
    (net (code "87") (name "/DAC_OUT_P16") (class "Default")
      (node (ref "J1") (pin "16") (pinfunction "16_16") (pintype "bidirectional"))
      (node (ref "J4") (pin "22") (pinfunction "22_22") (pintype "bidirectional"))
    )
    (net (code "88") (name "/DAC_OUT_P17") (class "Default")
      (node (ref "J1") (pin "19") (pinfunction "19_19") (pintype "bidirectional"))
      (node (ref "J5") (pin "1") (pinfunction "1_1") (pintype "bidirectional"))
    )
    (net (code "89") (name "/DAC_OUT_P18") (class "Default")
      (node (ref "J1") (pin "20") (pinfunction "20_20") (pintype "bidirectional"))
      (node (ref "J5") (pin "4") (pinfunction "4_4") (pintype "bidirectional"))
    )
    (net (code "90") (name "/DAC_OUT_P19") (class "Default")
      (node (ref "J1") (pin "21") (pinfunction "21_21") (pintype "bidirectional"))
      (node (ref "J5") (pin "7") (pinfunction "7_7") (pintype "bidirectional"))
    )
    (net (code "91") (name "/DAC_OUT_P20") (class "Default")
      (node (ref "J1") (pin "22") (pinfunction "22_22") (pintype "bidirectional"))
      (node (ref "J5") (pin "10") (pinfunction "10_10") (pintype "bidirectional"))
    )
    (net (code "92") (name "/DAC_OUT_P21") (class "Default")
      (node (ref "J1") (pin "23") (pinfunction "23_23") (pintype "bidirectional"))
      (node (ref "J5") (pin "13") (pinfunction "13_13") (pintype "bidirectional"))
    )
    (net (code "93") (name "/DAC_OUT_P22") (class "Default")
      (node (ref "J1") (pin "24") (pinfunction "24_24") (pintype "bidirectional"))
      (node (ref "J5") (pin "16") (pinfunction "16_16") (pintype "bidirectional"))
    )
    (net (code "94") (name "/DAC_OUT_P23") (class "Default")
      (node (ref "J1") (pin "25") (pinfunction "25_25") (pintype "bidirectional"))
      (node (ref "J5") (pin "19") (pinfunction "19_19") (pintype "bidirectional"))
    )
    (net (code "95") (name "/DAC_OUT_P24") (class "Default")
      (node (ref "J1") (pin "26") (pinfunction "26_26") (pintype "bidirectional"))
      (node (ref "J5") (pin "22") (pinfunction "22_22") (pintype "bidirectional"))
    )
    (net (code "96") (name "/DAC_OUT_P25") (class "Default")
      (node (ref "J1") (pin "27") (pinfunction "27_27") (pintype "bidirectional"))
      (node (ref "J7") (pin "1") (pinfunction "1_1") (pintype "bidirectional"))
    )
    (net (code "97") (name "/DAC_OUT_P26") (class "Default")
      (node (ref "J1") (pin "28") (pinfunction "28_28") (pintype "bidirectional"))
      (node (ref "J7") (pin "4") (pinfunction "4_4") (pintype "bidirectional"))
    )
    (net (code "98") (name "/DAC_OUT_P27") (class "Default")
      (node (ref "J1") (pin "29") (pinfunction "29_29") (pintype "bidirectional"))
      (node (ref "J7") (pin "7") (pinfunction "7_7") (pintype "bidirectional"))
    )
    (net (code "99") (name "/DAC_OUT_P28") (class "Default")
      (node (ref "J1") (pin "30") (pinfunction "30_30") (pintype "bidirectional"))
      (node (ref "J7") (pin "10") (pinfunction "10_10") (pintype "bidirectional"))
    )
    (net (code "100") (name "/DAC_OUT_P29") (class "Default")
      (node (ref "J1") (pin "31") (pinfunction "31_31") (pintype "bidirectional"))
      (node (ref "J7") (pin "13") (pinfunction "13_13") (pintype "bidirectional"))
    )
    (net (code "101") (name "/DAC_OUT_P30") (class "Default")
      (node (ref "J1") (pin "32") (pinfunction "32_32") (pintype "bidirectional"))
      (node (ref "J7") (pin "16") (pinfunction "16_16") (pintype "bidirectional"))
    )
    (net (code "102") (name "/DAC_OUT_P31") (class "Default")
      (node (ref "J1") (pin "33") (pinfunction "33_33") (pintype "bidirectional"))
      (node (ref "J7") (pin "19") (pinfunction "19_19") (pintype "bidirectional"))
    )
    (net (code "103") (name "/DAC_OUT_P32") (class "Default")
      (node (ref "J1") (pin "34") (pinfunction "34_34") (pintype "bidirectional"))
      (node (ref "J7") (pin "22") (pinfunction "22_22") (pintype "bidirectional"))
    )
    (net (code "105") (name "/I2C_SCL") (class "Default")
      (node (ref "J2") (pin "16") (pinfunction "16_16") (pintype "bidirectional"))
    )
    (net (code "106") (name "/I2C_SDA") (class "Default")
      (node (ref "J2") (pin "15") (pinfunction "15_15") (pintype "bidirectional"))
    )
    (net (code "108") (name "/LED0") (class "Default")
      (node (ref "IC23") (pin "15") (pinfunction "QA_15") (pintype "tri_state"))
      (node (ref "R113") (pin "1") (pinfunction "1_1") (pintype "passive"))
    )
    (net (code "109") (name "/LED1") (class "Default")
      (node (ref "IC23") (pin "1") (pinfunction "QB_1") (pintype "tri_state"))
      (node (ref "R114") (pin "1") (pinfunction "1_1") (pintype "passive"))
    )
    (net (code "110") (name "/LED2") (class "Default")
      (node (ref "IC23") (pin "2") (pinfunction "QC_2") (pintype "tri_state"))
      (node (ref "R115") (pin "1") (pinfunction "1_1") (pintype "passive"))
    )
    (net (code "111") (name "/LED3") (class "Default")
      (node (ref "IC23") (pin "3") (pinfunction "QD_3") (pintype "tri_state"))
      (node (ref "R119") (pin "1") (pinfunction "1_1") (pintype "passive"))
    )
    (net (code "112") (name "/LED4") (class "Default")
      (node (ref "IC23") (pin "4") (pinfunction "QE_4") (pintype "tri_state"))
      (node (ref "R120") (pin "1") (pinfunction "1_1") (pintype "passive"))
    )
    (net (code "113") (name "/LED5") (class "Default")
      (node (ref "IC23") (pin "5") (pinfunction "QF_5") (pintype "tri_state"))
      (node (ref "R121") (pin "1") (pinfunction "1_1") (pintype "passive"))
    )
    (net (code "114") (name "/LED6") (class "Default")
      (node (ref "IC23") (pin "6") (pinfunction "QG_6") (pintype "tri_state"))
      (node (ref "R122") (pin "1") (pinfunction "1_1") (pintype "passive"))
    )
    (net (code "115") (name "/LED7") (class "Default")
      (node (ref "IC23") (pin "7") (pinfunction "QH_7") (pintype "tri_state"))
      (node (ref "R123") (pin "1") (pinfunction "1_1") (pintype "passive"))
    )
    (net (code "116") (name "/RESETn") (class "Default")
      (node (ref "IC19") (pin "2") (pinfunction "~{RST}_2") (pintype "output"))
    )
    (net (code "117") (name "/SCKI") (class "Default")
      (node (ref "IC23") (pin "11") (pinfunction "SRCLK_11") (pintype "input"))
      (node (ref "R117") (pin "2") (pinfunction "2_2") (pintype "passive"))
    )
    (net (code "118") (name "/SDI") (class "Default")
      (node (ref "IC23") (pin "14") (pinfunction "SER_14") (pintype "input"))
      (node (ref "R116") (pin "2") (pinfunction "2_2") (pintype "passive"))
    )
    (net (code "120") (name "/TEC+") (class "Default")
      (node (ref "B5") (pin "1") (pinfunction "1_1") (pintype "bidirectional"))
      (node (ref "J2") (pin "4") (pinfunction "4_4") (pintype "bidirectional"))
      (node (ref "J2") (pin "6") (pinfunction "6_6") (pintype "bidirectional"))
      (node (ref "J2") (pin "8") (pinfunction "8_8") (pintype "bidirectional"))
    )
    (net (code "121") (name "/TEC-") (class "Default")
      (node (ref "B6") (pin "1") (pinfunction "1_1") (pintype "bidirectional"))
      (node (ref "J2") (pin "5") (pinfunction "5_5") (pintype "bidirectional"))
      (node (ref "J2") (pin "7") (pinfunction "7_7") (pintype "bidirectional"))
      (node (ref "J2") (pin "9") (pinfunction "9_9") (pintype "bidirectional"))
    )
    (net (code "124") (name "GND") (class "Default")
      (node (ref "C68") (pin "1") (pinfunction "1_1") (pintype "passive"))
      (node (ref "C71") (pin "1") (pinfunction "1_1") (pintype "passive"))
      (node (ref "C95") (pin "1") (pinfunction "1_1") (pintype "passive"))
      (node (ref "C96") (pin "1") (pinfunction "1_1") (pintype "passive"))
      (node (ref "CLIP27") (pin "1") (pinfunction "1_1") (pintype "passive"))
      (node (ref "CLIP28") (pin "1") (pinfunction "1_1") (pintype "passive"))
      (node (ref "CLIP29") (pin "1") (pinfunction "1_1") (pintype "passive"))
      (node (ref "CLIP30") (pin "1") (pinfunction "1_1") (pintype "passive"))
      (node (ref "CLIP31") (pin "1") (pinfunction "1_1") (pintype "passive"))
      (node (ref "CLIP32") (pin "1") (pinfunction "1_1") (pintype "passive"))
      (node (ref "CLIP33") (pin "1") (pinfunction "1_1") (pintype "passive"))
      (node (ref "CLIP34") (pin "1") (pinfunction "1_1") (pintype "passive"))
      (node (ref "CLIP35") (pin "1") (pinfunction "1_1") (pintype "passive"))
      (node (ref "CLIP36") (pin "1") (pinfunction "1_1") (pintype "passive"))
      (node (ref "CLIP37") (pin "1") (pinfunction "1_1") (pintype "passive"))
      (node (ref "CLIP38") (pin "1") (pinfunction "1_1") (pintype "passive"))
      (node (ref "CLIP39") (pin "1") (pinfunction "1_1") (pintype "passive"))
      (node (ref "CLIP40") (pin "1") (pinfunction "1_1") (pintype "passive"))
      (node (ref "CLIP41") (pin "1") (pinfunction "1_1") (pintype "passive"))
      (node (ref "CLIP42") (pin "1") (pinfunction "1_1") (pintype "passive"))
      (node (ref "CLIP43") (pin "1") (pinfunction "1_1") (pintype "passive"))
      (node (ref "CLIP44") (pin "1") (pinfunction "1_1") (pintype "passive"))
      (node (ref "CLIP45") (pin "1") (pinfunction "1_1") (pintype "passive"))
      (node (ref "CLIP46") (pin "1") (pinfunction "1_1") (pintype "passive"))
      (node (ref "CLIP47") (pin "1") (pinfunction "1_1") (pintype "passive"))
      (node (ref "CLIP48") (pin "1") (pinfunction "1_1") (pintype "passive"))
      (node (ref "CLIP49") (pin "1") (pinfunction "1_1") (pintype "passive"))
      (node (ref "CLIP50") (pin "1") (pinfunction "1_1") (pintype "passive"))
      (node (ref "CLIP51") (pin "1") (pinfunction "1_1") (pintype "passive"))
      (node (ref "CLIP52") (pin "1") (pinfunction "1_1") (pintype "passive"))
      (node (ref "IC19") (pin "1") (pinfunction "VSS_1") (pintype "power_in"))
      (node (ref "IC23") (pin "13") (pinfunction "~{OE}_13") (pintype "input"))
      (node (ref "IC23") (pin "8") (pinfunction "GND_8") (pintype "power_in"))
      (node (ref "J1") (pin "17") (pinfunction "17_17") (pintype "bidirectional"))
      (node (ref "J1") (pin "51") (pinfunction "51_51") (pintype "bidirectional"))
      (node (ref "J1") (pin "69") (pinfunction "69_69") (pintype "bidirectional"))
      (node (ref "J1") (pin "70") (pinfunction "70_70") (pintype "bidirectional"))
      (node (ref "J2") (pin "12") (pinfunction "12_12") (pintype "bidirectional"))
      (node (ref "J2") (pin "13") (pinfunction "13_13") (pintype "bidirectional"))
      (node (ref "J2") (pin "3") (pinfunction "3_3") (pintype "bidirectional"))
      (node (ref "J3") (pin "12") (pinfunction "12_12") (pintype "bidirectional"))
      (node (ref "J3") (pin "15") (pinfunction "15_15") (pintype "bidirectional"))
      (node (ref "J3") (pin "18") (pinfunction "18_18") (pintype "bidirectional"))
      (node (ref "J3") (pin "21") (pinfunction "21_21") (pintype "bidirectional"))
      (node (ref "J3") (pin "24") (pinfunction "24_24") (pintype "bidirectional"))
      (node (ref "J3") (pin "3") (pinfunction "3_3") (pintype "bidirectional"))
      (node (ref "J3") (pin "6") (pinfunction "6_6") (pintype "bidirectional"))
      (node (ref "J3") (pin "9") (pinfunction "9_9") (pintype "bidirectional"))
      (node (ref "J4") (pin "12") (pinfunction "12_12") (pintype "bidirectional"))
      (node (ref "J4") (pin "15") (pinfunction "15_15") (pintype "bidirectional"))
      (node (ref "J4") (pin "18") (pinfunction "18_18") (pintype "bidirectional"))
      (node (ref "J4") (pin "21") (pinfunction "21_21") (pintype "bidirectional"))
      (node (ref "J4") (pin "24") (pinfunction "24_24") (pintype "bidirectional"))
      (node (ref "J4") (pin "3") (pinfunction "3_3") (pintype "bidirectional"))
      (node (ref "J4") (pin "6") (pinfunction "6_6") (pintype "bidirectional"))
      (node (ref "J4") (pin "9") (pinfunction "9_9") (pintype "bidirectional"))
      (node (ref "J5") (pin "12") (pinfunction "12_12") (pintype "bidirectional"))
      (node (ref "J5") (pin "15") (pinfunction "15_15") (pintype "bidirectional"))
      (node (ref "J5") (pin "18") (pinfunction "18_18") (pintype "bidirectional"))
      (node (ref "J5") (pin "21") (pinfunction "21_21") (pintype "bidirectional"))
      (node (ref "J5") (pin "24") (pinfunction "24_24") (pintype "bidirectional"))
      (node (ref "J5") (pin "3") (pinfunction "3_3") (pintype "bidirectional"))
      (node (ref "J5") (pin "6") (pinfunction "6_6") (pintype "bidirectional"))
      (node (ref "J5") (pin "9") (pinfunction "9_9") (pintype "bidirectional"))
      (node (ref "J7") (pin "12") (pinfunction "12_12") (pintype "bidirectional"))
      (node (ref "J7") (pin "15") (pinfunction "15_15") (pintype "bidirectional"))
      (node (ref "J7") (pin "18") (pinfunction "18_18") (pintype "bidirectional"))
      (node (ref "J7") (pin "21") (pinfunction "21_21") (pintype "bidirectional"))
      (node (ref "J7") (pin "24") (pinfunction "24_24") (pintype "bidirectional"))
      (node (ref "J7") (pin "3") (pinfunction "3_3") (pintype "bidirectional"))
      (node (ref "J7") (pin "6") (pinfunction "6_6") (pintype "bidirectional"))
      (node (ref "J7") (pin "9") (pinfunction "9_9") (pintype "bidirectional"))
      (node (ref "LD4") (pin "1") (pinfunction "C_1") (pintype "passive"))
      (node (ref "LD4") (pin "3") (pinfunction "C_3") (pintype "passive"))
      (node (ref "LD4") (pin "5") (pinfunction "C_5") (pintype "passive"))
      (node (ref "LD4") (pin "7") (pinfunction "C_7") (pintype "passive"))
      (node (ref "LD5") (pin "1") (pinfunction "C_1") (pintype "passive"))
      (node (ref "LD5") (pin "3") (pinfunction "C_3") (pintype "passive"))
      (node (ref "LD5") (pin "5") (pinfunction "C_5") (pintype "passive"))
      (node (ref "LD5") (pin "7") (pinfunction "C_7") (pintype "passive"))
      (node (ref "R10") (pin "1") (pinfunction "1_1") (pintype "passive"))
      (node (ref "R10") (pin "2") (pinfunction "2_2") (pintype "passive"))
      (node (ref "R12") (pin "1") (pinfunction "1_1") (pintype "passive"))
      (node (ref "R12") (pin "2") (pinfunction "2_2") (pintype "passive"))
      (node (ref "R8") (pin "1") (pinfunction "1_1") (pintype "passive"))
      (node (ref "R8") (pin "2") (pinfunction "2_2") (pintype "passive"))
      (node (ref "R9") (pin "1") (pinfunction "1_1") (pintype "passive"))
      (node (ref "R9") (pin "2") (pinfunction "2_2") (pintype "passive"))
    )
    (net (code "125") (name "N13V0_SCSI") (class "Default")
      (node (ref "J1") (pin "52") (pinfunction "52_52") (pintype "bidirectional"))
      (node (ref "J3") (pin "26") (pinfunction "26_26") (pintype "bidirectional"))
      (node (ref "J4") (pin "26") (pinfunction "26_26") (pintype "bidirectional"))
      (node (ref "J5") (pin "26") (pinfunction "26_26") (pintype "bidirectional"))
      (node (ref "J7") (pin "26") (pinfunction "26_26") (pintype "bidirectional"))
    )
    (net (code "126") (name "Net-(C68-Pad2)") (class "Default")
      (node (ref "C68") (pin "2") (pinfunction "2_2") (pintype "passive"))
      (node (ref "R117") (pin "1") (pinfunction "1_1") (pintype "passive"))
    )
    (net (code "127") (name "Net-(C71-Pad2)") (class "Default")
      (node (ref "C71") (pin "2") (pinfunction "2_2") (pintype "passive"))
      (node (ref "R118") (pin "1") (pinfunction "1_1") (pintype "passive"))
    )
    (net (code "128") (name "Net-(C95-Pad2)") (class "Default")
      (node (ref "C95") (pin "2") (pinfunction "2_2") (pintype "passive"))
      (node (ref "R116") (pin "1") (pinfunction "1_1") (pintype "passive"))
    )
    (net (code "129") (name "Net-(J2-Pad1)") (class "Default")
      (node (ref "J2") (pin "1") (pinfunction "1_1") (pintype "bidirectional"))
      (node (ref "RT1") (pin "1") (pinfunction "1_1") (pintype "passive"))
    )
    (net (code "130") (name "Net-(J2-Pad2)") (class "Default")
      (node (ref "J2") (pin "2") (pinfunction "2_2") (pintype "bidirectional"))
      (node (ref "RT1") (pin "2") (pinfunction "2_2") (pintype "passive"))
    )
    (net (code "131") (name "Net-(LD4A-A)") (class "Default")
      (node (ref "LD4") (pin "2") (pinfunction "A_2") (pintype "passive"))
      (node (ref "R113") (pin "2") (pinfunction "2_2") (pintype "passive"))
    )
    (net (code "132") (name "Net-(LD4B-A)") (class "Default")
      (node (ref "LD4") (pin "4") (pinfunction "A_4") (pintype "passive"))
      (node (ref "R114") (pin "2") (pinfunction "2_2") (pintype "passive"))
    )
    (net (code "133") (name "Net-(LD4C-A)") (class "Default")
      (node (ref "LD4") (pin "6") (pinfunction "A_6") (pintype "passive"))
      (node (ref "R115") (pin "2") (pinfunction "2_2") (pintype "passive"))
    )
    (net (code "134") (name "Net-(LD4D-A)") (class "Default")
      (node (ref "LD4") (pin "8") (pinfunction "A_8") (pintype "passive"))
      (node (ref "R119") (pin "2") (pinfunction "2_2") (pintype "passive"))
    )
    (net (code "135") (name "Net-(LD5A-A)") (class "Default")
      (node (ref "LD5") (pin "2") (pinfunction "A_2") (pintype "passive"))
      (node (ref "R120") (pin "2") (pinfunction "2_2") (pintype "passive"))
    )
    (net (code "136") (name "Net-(LD5B-A)") (class "Default")
      (node (ref "LD5") (pin "4") (pinfunction "A_4") (pintype "passive"))
      (node (ref "R121") (pin "2") (pinfunction "2_2") (pintype "passive"))
    )
    (net (code "137") (name "Net-(LD5C-A)") (class "Default")
      (node (ref "LD5") (pin "6") (pinfunction "A_6") (pintype "passive"))
      (node (ref "R122") (pin "2") (pinfunction "2_2") (pintype "passive"))
    )
    (net (code "138") (name "Net-(LD5D-A)") (class "Default")
      (node (ref "LD5") (pin "8") (pinfunction "A_8") (pintype "passive"))
      (node (ref "R123") (pin "2") (pinfunction "2_2") (pintype "passive"))
    )
    (net (code "139") (name "P3V3") (class "Default")
      (node (ref "C96") (pin "2") (pinfunction "2_2") (pintype "passive"))
      (node (ref "IC19") (pin "3") (pinfunction "~{MR}_3") (pintype "input"))
      (node (ref "IC19") (pin "4") (pinfunction "VCC_4") (pintype "power_in"))
      (node (ref "IC23") (pin "10") (pinfunction "~{SRCLR}_10") (pintype "input"))
      (node (ref "IC23") (pin "16") (pinfunction "VCC_16") (pintype "power_in"))
    )
    (net (code "140") (name "P3V3_MP") (class "Default")
      (node (ref "J2") (pin "14") (pinfunction "14_14") (pintype "bidirectional"))
    )
    (net (code "141") (name "P12V0") (class "Default")
      (node (ref "J2") (pin "10") (pinfunction "10_10") (pintype "bidirectional"))
      (node (ref "J2") (pin "11") (pinfunction "11_11") (pintype "bidirectional"))
    )
    (net (code "142") (name "P13V0_SCSI") (class "Default")
      (node (ref "J1") (pin "18") (pinfunction "18_18") (pintype "bidirectional"))
      (node (ref "J3") (pin "25") (pinfunction "25_25") (pintype "bidirectional"))
      (node (ref "J4") (pin "25") (pinfunction "25_25") (pintype "bidirectional"))
      (node (ref "J5") (pin "25") (pinfunction "25_25") (pintype "bidirectional"))
      (node (ref "J7") (pin "25") (pinfunction "25_25") (pintype "bidirectional"))
    )
    (net (code "143") (name "unconnected-(B2-Pad1)") (class "Default")
      (node (ref "B2") (pin "1") (pinfunction "1_1") (pintype "bidirectional"))
    )
    (net (code "144") (name "unconnected-(B3-Pad1)") (class "Default")
      (node (ref "B3") (pin "1") (pinfunction "1_1") (pintype "bidirectional"))
    )
    (net (code "145") (name "unconnected-(B4-Pad1)") (class "Default")
      (node (ref "B4") (pin "1") (pinfunction "1_1") (pintype "bidirectional"))
    )
    (net (code "146") (name "unconnected-(B8-Pad1)") (class "Default")
      (node (ref "B8") (pin "1") (pinfunction "1_1") (pintype "bidirectional"))
    )
    (net (code "147") (name "unconnected-(B9-Pad1)") (class "Default")
      (node (ref "B9") (pin "1") (pinfunction "1_1") (pintype "bidirectional"))
    )
    (net (code "148") (name "unconnected-(B10-Pad1)") (class "Default")
      (node (ref "B10") (pin "1") (pinfunction "1_1") (pintype "bidirectional"))
    )
    (net (code "149") (name "unconnected-(IC23-QH'-Pad9)") (class "Default")
      (node (ref "IC23") (pin "9") (pinfunction "QH'_9") (pintype "output"))
    )
  )
)
